# DAC_OUT.net
KiCad netlist of a schematic drawn in Altium Designer
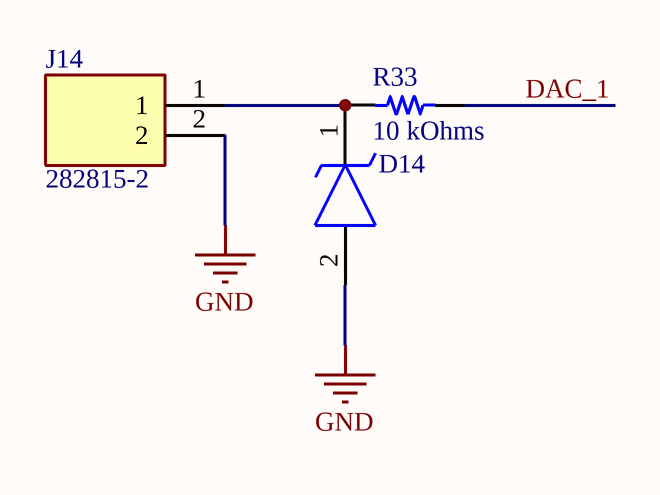
[diagram p0: DAC_OUT.SchDoc]

(export (version "E")
  (design (tool "Eeschema 10.0.6"))
  (components
    (comp (ref "D14")
      (value "SMBJ5.0A")
      (footprint "SamacSys:SMBJ12A")
      (description "TVS Diode (Uni-directional)")
      (libsource (lib "*") (part "SMBJ5.0A"))
    )
    (comp (ref "J14")
      (value "282815-2")
      (footprint "SamacSys:SHDRRA2W102P0X508_1X2_1016X1200X850P")
      (description "Connector")
      (fields (field (name "MOUSER PART NUMBER") "571-282815-2"))
      (libsource (lib "*") (part "282815-2"))
    )
    (comp (ref "R33")
      (value "10 kOhms")
      (footprint "RES 0603_1608")
      (description "RES SMD 10K OHM 1% 1/10W 0603")
      (fields (field (name "PART NUMBER") "RT0603FRE0710KL") (field (name "MANUFACTURER") "Yageo"))
      (libsource (lib "dc_ups") (part "RT0603FRE0710KL"))
    )
  )
  (nets
    (net (code "1") (name "/DAC_1") (class "Default")
      (node (ref "R33") (pin "1") (pinfunction "1_1") (pintype "passive"))
    )
    (net (code "2") (name "GND") (class "Default")
      (node (ref "D14") (pin "2") (pinfunction "A_2") (pintype "passive"))
      (node (ref "J14") (pin "2") (pinfunction "2_2") (pintype "passive"))
    )
    (net (code "3") (name "Net-(D14-K)") (class "Default")
      (node (ref "D14") (pin "1") (pinfunction "K_1") (pintype "passive"))
      (node (ref "J14") (pin "1") (pinfunction "1_1") (pintype "passive"))
      (node (ref "R33") (pin "2") (pinfunction "2_2") (pintype "passive"))
    )
  )
)
